# LightingUPS_v2.net
KiCad netlist of a schematic drawn in EAGLE
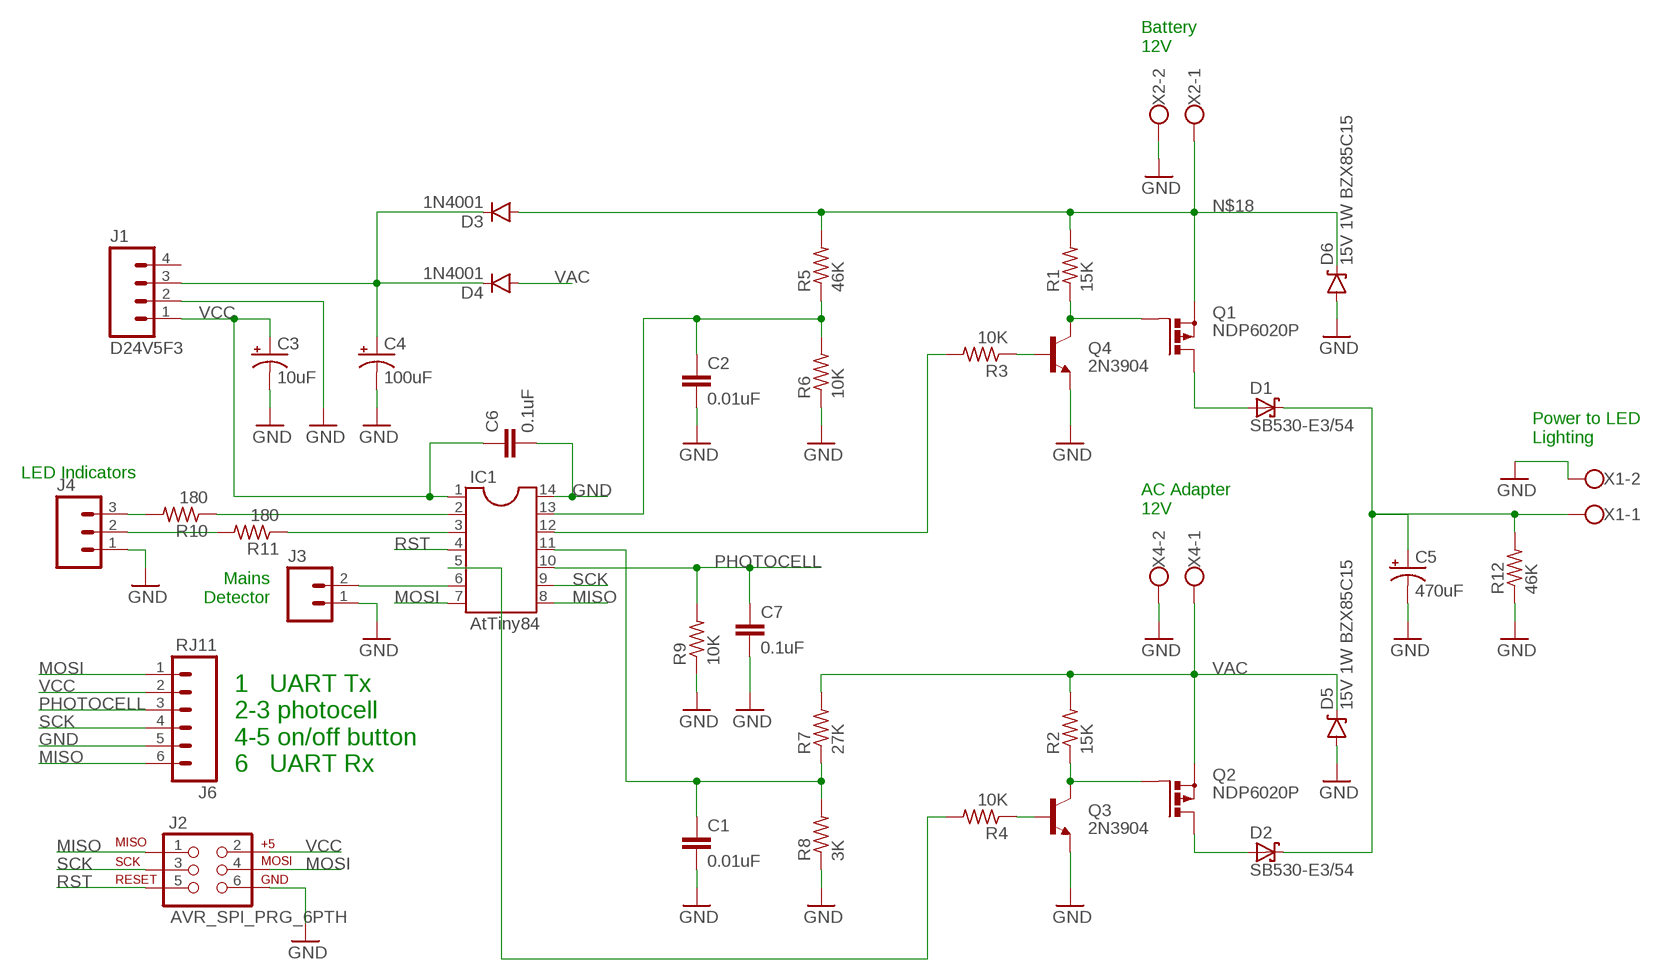
[diagram p0: schematic, sheet 1]

(export (version "E")
  (design (tool "Eeschema 10.0.6"))
  (components
    (comp (ref "C1")
      (value "0.01uF")
      (footprint "eagle-import:CAP-PTH-5MM")
      (libsource (lib "eagle-import") (part "SparkFun-Passives_CAPPTH1"))
    )
    (comp (ref "C2")
      (value "0.01uF")
      (footprint "eagle-import:CAP-PTH-5MM")
      (libsource (lib "eagle-import") (part "SparkFun-Passives_CAPPTH1"))
    )
    (comp (ref "C3")
      (value "10uF")
      (footprint "eagle-import:CPOL-RADIAL-100UF-25V")
      (libsource (lib "eagle-import") (part "CAP_POLPTH1"))
    )
    (comp (ref "C4")
      (value "100uF")
      (footprint "eagle-import:CPOL-RADIAL-100UF-25V")
      (libsource (lib "eagle-import") (part "CAP_POLPTH1"))
    )
    (comp (ref "C5")
      (value "470uF")
      (footprint "eagle-import:CPOL-RADIAL-1000UF-25V")
      (libsource (lib "eagle-import") (part "CAP_POLPTH4"))
    )
    (comp (ref "C6")
      (value "0.1uF")
      (footprint "eagle-import:CAP-PTH-SMALL")
      (libsource (lib "eagle-import") (part "CAPPTH"))
    )
    (comp (ref "C7")
      (value "0.1uF")
      (footprint "eagle-import:CAP-PTH-SMALL")
      (libsource (lib "eagle-import") (part "CAPPTH"))
    )
    (comp (ref "D1")
      (value "SB530-E3/54")
      (footprint "eagle-import:DO201T15")
      (libsource (lib "eagle-import") (part "SCHOTTKY-DIODEDO201T15"))
    )
    (comp (ref "D2")
      (value "SB530-E3/54")
      (footprint "eagle-import:DO201T15")
      (libsource (lib "eagle-import") (part "SCHOTTKY-DIODEDO201T15"))
    )
    (comp (ref "D3")
      (value "1N4001")
      (footprint "eagle-import:DIODE-1N4001")
      (libsource (lib "eagle-import") (part "DIODEPTH"))
    )
    (comp (ref "D4")
      (value "1N4001")
      (footprint "eagle-import:DIODE-1N4001")
      (libsource (lib "eagle-import") (part "DIODEPTH"))
    )
    (comp (ref "D5")
      (value "15V 1W BZX85C15")
      (footprint "eagle-import:DIODE-ZENER")
      (libsource (lib "eagle-import") (part "DIODE-ZENERPTH"))
    )
    (comp (ref "D6")
      (value "15V 1W BZX85C15")
      (footprint "eagle-import:DIODE-ZENER")
      (libsource (lib "eagle-import") (part "DIODE-ZENERPTH"))
    )
    (comp (ref "IC1")
      (value "AtTiny84")
      (footprint "eagle-import:DIL14")
      (libsource (lib "eagle-import") (part "DIL14"))
    )
    (comp (ref "J1")
      (value "D24V5F3")
      (footprint "eagle-import:1X04")
      (libsource (lib "eagle-import") (part "M04PTH"))
    )
    (comp (ref "J2")
      (value "AVR_SPI_PRG_6PTH")
      (footprint "eagle-import:2X3")
      (libsource (lib "eagle-import") (part "AVR_SPI_PRG_6PTH"))
    )
    (comp (ref "J3")
      (value "M02PTH")
      (footprint "eagle-import:1X02")
      (libsource (lib "eagle-import") (part "M02PTH"))
    )
    (comp (ref "J4")
      (value "M03PTH")
      (footprint "eagle-import:1X03")
      (libsource (lib "eagle-import") (part "M03PTH"))
    )
    (comp (ref "J6")
      (value "RJ11")
      (footprint "eagle-import:RJ11-6")
      (libsource (lib "eagle-import") (part "RJ11-6PTH"))
    )
    (comp (ref "Q1")
      (value "NDP6020P")
      (footprint "eagle-import:TO220BV")
      (libsource (lib "eagle-import") (part "PMOSFET_PTO220BV"))
    )
    (comp (ref "Q2")
      (value "NDP6020P")
      (footprint "eagle-import:TO220BV")
      (libsource (lib "eagle-import") (part "PMOSFET_PTO220BV"))
    )
    (comp (ref "Q3")
      (value "2N3904")
      (footprint "eagle-import:TO-92-AMMO")
      (libsource (lib "eagle-import") (part "TRANSISTOR_NPNTO-92-AMMO"))
    )
    (comp (ref "Q4")
      (value "2N3904")
      (footprint "eagle-import:TO-92-AMMO")
      (libsource (lib "eagle-import") (part "TRANSISTOR_NPNTO-92-AMMO"))
    )
    (comp (ref "R1")
      (value "15K")
      (footprint "eagle-import:0204_5")
      (libsource (lib "eagle-import") (part "R-US_0204/5"))
    )
    (comp (ref "R2")
      (value "15K")
      (footprint "eagle-import:0204_5")
      (libsource (lib "eagle-import") (part "R-US_0204/5"))
    )
    (comp (ref "R3")
      (value "10K")
      (footprint "eagle-import:0204_5")
      (libsource (lib "eagle-import") (part "R-US_0204/5"))
    )
    (comp (ref "R4")
      (value "10K")
      (footprint "eagle-import:0204_5")
      (libsource (lib "eagle-import") (part "R-US_0204/5"))
    )
    (comp (ref "R5")
      (value "46K")
      (footprint "eagle-import:0204_5")
      (libsource (lib "eagle-import") (part "R-US_0204/5"))
    )
    (comp (ref "R6")
      (value "10K")
      (footprint "eagle-import:0204_5")
      (libsource (lib "eagle-import") (part "R-US_0204/5"))
    )
    (comp (ref "R7")
      (value "27K")
      (footprint "eagle-import:0204_5")
      (libsource (lib "eagle-import") (part "R-US_0204/5"))
    )
    (comp (ref "R8")
      (value "3K")
      (footprint "eagle-import:0204_5")
      (libsource (lib "eagle-import") (part "R-US_0204/5"))
    )
    (comp (ref "R9")
      (value "10K")
      (footprint "eagle-import:0204_5")
      (libsource (lib "eagle-import") (part "R-US_0204/5"))
    )
    (comp (ref "R10")
      (value "180")
      (footprint "eagle-import:0204_5")
      (libsource (lib "eagle-import") (part "R-US_0204/5"))
    )
    (comp (ref "R11")
      (value "180")
      (footprint "eagle-import:0204_5")
      (libsource (lib "eagle-import") (part "R-US_0204/5"))
    )
    (comp (ref "R12")
      (value "46K")
      (footprint "eagle-import:0204_5")
      (libsource (lib "eagle-import") (part "R-US_0204/5"))
    )
    (comp (ref "X1")
      (value "W237-102")
      (footprint "eagle-import:W237-102")
      (fields (field (name "MPN") "237-102"))
      (libsource (lib "eagle-import") (part "W237-102"))
    )
    (comp (ref "X2")
      (value "W237-102")
      (footprint "eagle-import:W237-102")
      (fields (field (name "MPN") "237-102"))
      (libsource (lib "eagle-import") (part "W237-102"))
    )
    (comp (ref "X4")
      (value "W237-102")
      (footprint "eagle-import:W237-102")
      (fields (field (name "MPN") "237-102"))
      (libsource (lib "eagle-import") (part "W237-102"))
    )
  )
  (nets
    (net (code "1") (name "/MISO") (class "Default")
      (node (ref "IC1") (pin "8") (pinfunction "8_8") (pintype "passive"))
      (node (ref "J2") (pin "1") (pinfunction "1_1") (pintype "passive"))
      (node (ref "J6") (pin "6") (pinfunction "6_6") (pintype "passive"))
    )
    (net (code "2") (name "/MOSI") (class "Default")
      (node (ref "IC1") (pin "7") (pinfunction "7_7") (pintype "passive"))
      (node (ref "J2") (pin "4") (pinfunction "4_4") (pintype "passive"))
      (node (ref "J6") (pin "1") (pinfunction "1_1") (pintype "passive"))
    )
    (net (code "3") (name "/N$18") (class "Default")
      (node (ref "D3") (pin "A") (pinfunction "A_A") (pintype "passive"))
      (node (ref "D6") (pin "P$1") (pinfunction "C_P$1") (pintype "passive"))
      (node (ref "Q1") (pin "S") (pinfunction "S_S") (pintype "passive"))
      (node (ref "R1") (pin "2") (pinfunction "2_2") (pintype "passive"))
      (node (ref "R5") (pin "2") (pinfunction "2_2") (pintype "passive"))
      (node (ref "X2") (pin "1") (pinfunction "KL_1") (pintype "passive"))
    )
    (net (code "4") (name "/PHOTOCELL") (class "Default")
      (node (ref "C7") (pin "1") (pinfunction "1_1") (pintype "passive"))
      (node (ref "IC1") (pin "10") (pinfunction "10_10") (pintype "passive"))
      (node (ref "J6") (pin "3") (pinfunction "3_3") (pintype "passive"))
      (node (ref "R9") (pin "2") (pinfunction "2_2") (pintype "passive"))
    )
    (net (code "5") (name "/RST") (class "Default")
      (node (ref "IC1") (pin "4") (pinfunction "4_4") (pintype "passive"))
      (node (ref "J2") (pin "5") (pinfunction "5_5") (pintype "passive"))
    )
    (net (code "6") (name "/SCK") (class "Default")
      (node (ref "IC1") (pin "9") (pinfunction "9_9") (pintype "passive"))
      (node (ref "J2") (pin "3") (pinfunction "3_3") (pintype "passive"))
      (node (ref "J6") (pin "4") (pinfunction "4_4") (pintype "passive"))
    )
    (net (code "7") (name "/VAC") (class "Default")
      (node (ref "D4") (pin "A") (pinfunction "A_A") (pintype "passive"))
      (node (ref "D5") (pin "P$1") (pinfunction "C_P$1") (pintype "passive"))
      (node (ref "Q2") (pin "S") (pinfunction "S_S") (pintype "passive"))
      (node (ref "R2") (pin "2") (pinfunction "2_2") (pintype "passive"))
      (node (ref "R7") (pin "2") (pinfunction "2_2") (pintype "passive"))
      (node (ref "X4") (pin "1") (pinfunction "KL_1") (pintype "passive"))
    )
    (net (code "8") (name "/VCC") (class "Default")
      (node (ref "C3") (pin "1") (pinfunction "+_1") (pintype "passive"))
      (node (ref "C6") (pin "1") (pinfunction "1_1") (pintype "passive"))
      (node (ref "IC1") (pin "1") (pinfunction "1_1") (pintype "passive"))
      (node (ref "J1") (pin "1") (pinfunction "1_1") (pintype "passive"))
      (node (ref "J2") (pin "2") (pinfunction "2_2") (pintype "passive"))
      (node (ref "J6") (pin "2") (pinfunction "2_2") (pintype "passive"))
    )
    (net (code "9") (name "GND") (class "Default")
      (node (ref "C1") (pin "2") (pinfunction "2_2") (pintype "passive"))
      (node (ref "C2") (pin "2") (pinfunction "2_2") (pintype "passive"))
      (node (ref "C3") (pin "2") (pinfunction "-_2") (pintype "passive"))
      (node (ref "C4") (pin "2") (pinfunction "-_2") (pintype "passive"))
      (node (ref "C5") (pin "-") (pinfunction "-_-") (pintype "passive"))
      (node (ref "C6") (pin "2") (pinfunction "2_2") (pintype "passive"))
      (node (ref "C7") (pin "2") (pinfunction "2_2") (pintype "passive"))
      (node (ref "D5") (pin "P$2") (pinfunction "A_P$2") (pintype "passive"))
      (node (ref "D6") (pin "P$2") (pinfunction "A_P$2") (pintype "passive"))
      (node (ref "IC1") (pin "14") (pinfunction "14_14") (pintype "passive"))
      (node (ref "J1") (pin "2") (pinfunction "2_2") (pintype "passive"))
      (node (ref "J2") (pin "6") (pinfunction "6_6") (pintype "passive"))
      (node (ref "J3") (pin "1") (pinfunction "1_1") (pintype "passive"))
      (node (ref "J4") (pin "1") (pinfunction "1_1") (pintype "passive"))
      (node (ref "J6") (pin "5") (pinfunction "5_5") (pintype "passive"))
      (node (ref "Q3") (pin "1") (pinfunction "E_1") (pintype "passive"))
      (node (ref "Q4") (pin "1") (pinfunction "E_1") (pintype "passive"))
      (node (ref "R12") (pin "1") (pinfunction "1_1") (pintype "passive"))
      (node (ref "R6") (pin "1") (pinfunction "1_1") (pintype "passive"))
      (node (ref "R8") (pin "1") (pinfunction "1_1") (pintype "passive"))
      (node (ref "R9") (pin "1") (pinfunction "1_1") (pintype "passive"))
      (node (ref "X1") (pin "2") (pinfunction "KL_2") (pintype "passive"))
      (node (ref "X2") (pin "2") (pinfunction "KL_2") (pintype "passive"))
      (node (ref "X4") (pin "2") (pinfunction "KL_2") (pintype "passive"))
    )
    (net (code "10") (name "Net-(C1-Pad1)") (class "Default")
      (node (ref "C1") (pin "1") (pinfunction "1_1") (pintype "passive"))
      (node (ref "IC1") (pin "11") (pinfunction "11_11") (pintype "passive"))
      (node (ref "R7") (pin "1") (pinfunction "1_1") (pintype "passive"))
      (node (ref "R8") (pin "2") (pinfunction "2_2") (pintype "passive"))
    )
    (net (code "11") (name "Net-(C2-Pad1)") (class "Default")
      (node (ref "C2") (pin "1") (pinfunction "1_1") (pintype "passive"))
      (node (ref "IC1") (pin "13") (pinfunction "13_13") (pintype "passive"))
      (node (ref "R5") (pin "1") (pinfunction "1_1") (pintype "passive"))
      (node (ref "R6") (pin "2") (pinfunction "2_2") (pintype "passive"))
    )
    (net (code "12") (name "Net-(C4-+)") (class "Default")
      (node (ref "C4") (pin "1") (pinfunction "+_1") (pintype "passive"))
      (node (ref "D3") (pin "C") (pinfunction "C_C") (pintype "passive"))
      (node (ref "D4") (pin "C") (pinfunction "C_C") (pintype "passive"))
      (node (ref "J1") (pin "3") (pinfunction "3_3") (pintype "passive"))
    )
    (net (code "13") (name "Net-(D1-PadA)") (class "Default")
      (node (ref "D1") (pin "A") (pinfunction "A_A") (pintype "passive"))
      (node (ref "Q1") (pin "D") (pinfunction "D_D") (pintype "passive"))
    )
    (net (code "14") (name "Net-(D2-PadA)") (class "Default")
      (node (ref "D2") (pin "A") (pinfunction "A_A") (pintype "passive"))
      (node (ref "Q2") (pin "D") (pinfunction "D_D") (pintype "passive"))
    )
    (net (code "15") (name "Net-(IC1-Pad2)") (class "Default")
      (node (ref "IC1") (pin "2") (pinfunction "2_2") (pintype "passive"))
      (node (ref "R10") (pin "1") (pinfunction "1_1") (pintype "passive"))
    )
    (net (code "16") (name "Net-(IC1-Pad3)") (class "Default")
      (node (ref "IC1") (pin "3") (pinfunction "3_3") (pintype "passive"))
      (node (ref "R11") (pin "1") (pinfunction "1_1") (pintype "passive"))
    )
    (net (code "17") (name "Net-(IC1-Pad5)") (class "Default")
      (node (ref "IC1") (pin "5") (pinfunction "5_5") (pintype "passive"))
      (node (ref "R4") (pin "2") (pinfunction "2_2") (pintype "passive"))
    )
    (net (code "18") (name "Net-(IC1-Pad6)") (class "Default")
      (node (ref "IC1") (pin "6") (pinfunction "6_6") (pintype "passive"))
      (node (ref "J3") (pin "2") (pinfunction "2_2") (pintype "passive"))
    )
    (net (code "19") (name "Net-(IC1-Pad12)") (class "Default")
      (node (ref "IC1") (pin "12") (pinfunction "12_12") (pintype "passive"))
      (node (ref "R3") (pin "2") (pinfunction "2_2") (pintype "passive"))
    )
    (net (code "20") (name "Net-(J4-Pad2)") (class "Default")
      (node (ref "J4") (pin "2") (pinfunction "2_2") (pintype "passive"))
      (node (ref "R11") (pin "2") (pinfunction "2_2") (pintype "passive"))
    )
    (net (code "21") (name "Net-(J4-Pad3)") (class "Default")
      (node (ref "J4") (pin "3") (pinfunction "3_3") (pintype "passive"))
      (node (ref "R10") (pin "2") (pinfunction "2_2") (pintype "passive"))
    )
    (net (code "22") (name "Net-(Q3-B)") (class "Default")
      (node (ref "Q3") (pin "2") (pinfunction "B_2") (pintype "passive"))
      (node (ref "R4") (pin "1") (pinfunction "1_1") (pintype "passive"))
    )
    (net (code "23") (name "Net-(Q3-C)") (class "Default")
      (node (ref "Q2") (pin "G") (pinfunction "G_G") (pintype "passive"))
      (node (ref "Q3") (pin "3") (pinfunction "C_3") (pintype "passive"))
      (node (ref "R2") (pin "1") (pinfunction "1_1") (pintype "passive"))
    )
    (net (code "24") (name "Net-(Q4-B)") (class "Default")
      (node (ref "Q4") (pin "2") (pinfunction "B_2") (pintype "passive"))
      (node (ref "R3") (pin "1") (pinfunction "1_1") (pintype "passive"))
    )
    (net (code "25") (name "Net-(Q4-C)") (class "Default")
      (node (ref "Q1") (pin "G") (pinfunction "G_G") (pintype "passive"))
      (node (ref "Q4") (pin "3") (pinfunction "C_3") (pintype "passive"))
      (node (ref "R1") (pin "1") (pinfunction "1_1") (pintype "passive"))
    )
    (net (code "26") (name "Net-(X1A-KL)") (class "Default")
      (node (ref "C5") (pin "+") (pinfunction "+_+") (pintype "passive"))
      (node (ref "D1") (pin "C") (pinfunction "C_C") (pintype "passive"))
      (node (ref "D2") (pin "C") (pinfunction "C_C") (pintype "passive"))
      (node (ref "R12") (pin "2") (pinfunction "2_2") (pintype "passive"))
      (node (ref "X1") (pin "1") (pinfunction "KL_1") (pintype "passive"))
    )
    (net (code "27") (name "unconnected-(J1-Pad4)") (class "Default")
      (node (ref "J1") (pin "4") (pinfunction "4_4") (pintype "passive"))
    )
  )
)
